# MIDITheremin10-24.net
KiCad netlist of a schematic drawn in EAGLE
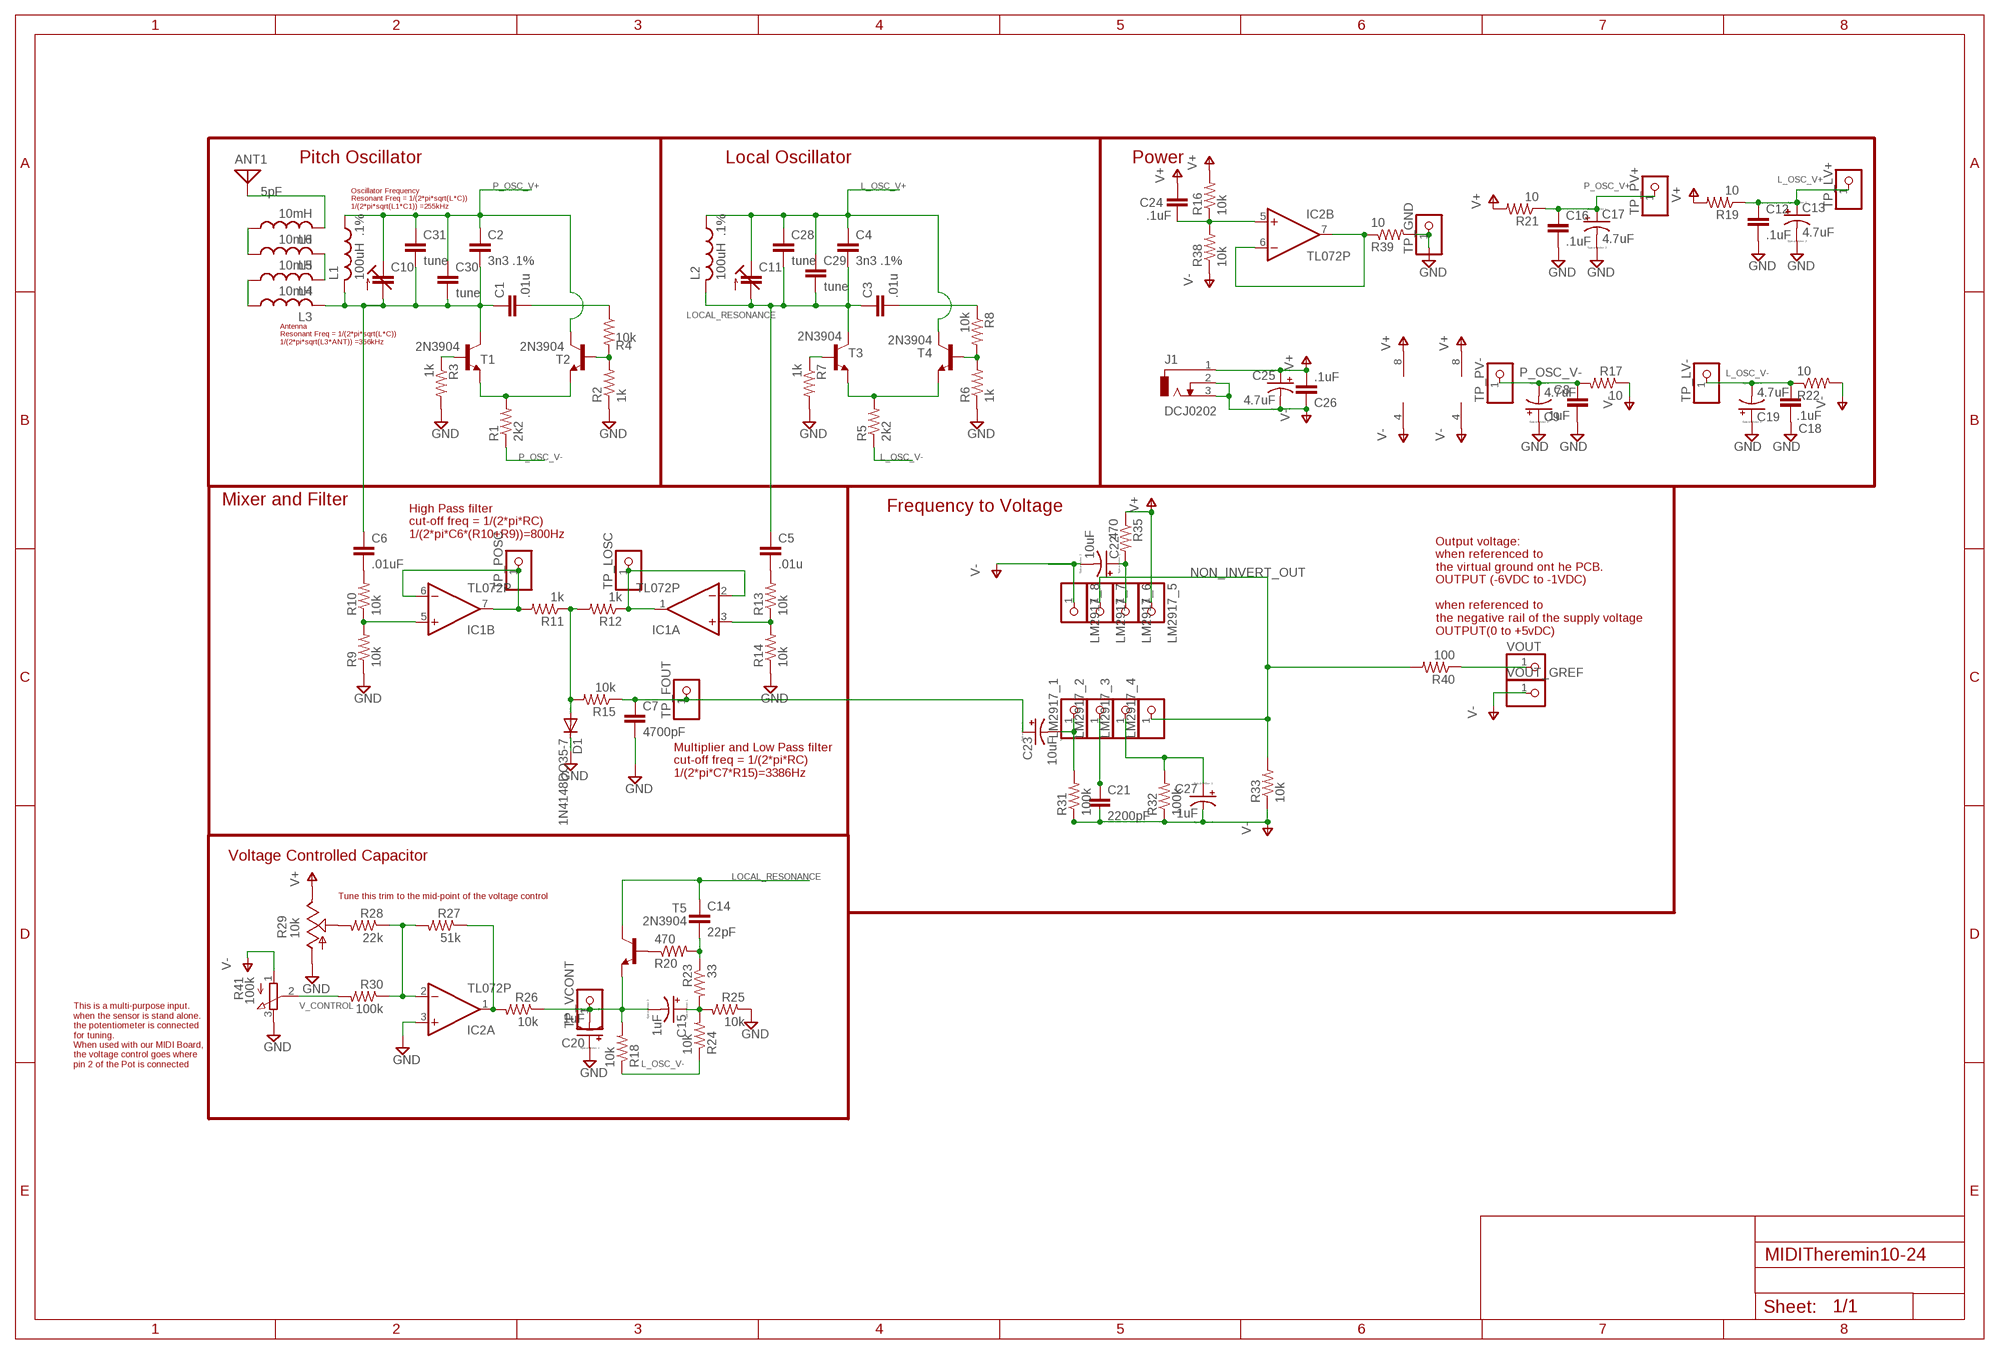
[diagram p0: schematic, sheet 1]

(export (version "E")
  (design (tool "Eeschema 10.0.6"))
  (components
    (comp (ref "ANT1")
      (value "5pF")
      (footprint "eagle-import:PAD-01")
      (libsource (lib "eagle-import") (part "ANTENNA"))
    )
    (comp (ref "C1")
      (value ".01u")
      (footprint "eagle-import:C050-025X075")
      (libsource (lib "eagle-import") (part "C-EU050-025X075"))
    )
    (comp (ref "C2")
      (value "3n3 .1%")
      (footprint "eagle-import:C050-025X075")
      (libsource (lib "eagle-import") (part "C-EU050-025X075"))
    )
    (comp (ref "C3")
      (value ".01u")
      (footprint "eagle-import:C050-025X075")
      (libsource (lib "eagle-import") (part "C-EU050-025X075"))
    )
    (comp (ref "C4")
      (value "3n3 .1%")
      (footprint "eagle-import:C050-025X075")
      (libsource (lib "eagle-import") (part "C-EU050-025X075"))
    )
    (comp (ref "C5")
      (value ".01u")
      (footprint "eagle-import:C050-025X075")
      (libsource (lib "eagle-import") (part "C-EU050-025X075"))
    )
    (comp (ref "C6")
      (value ".01uF")
      (footprint "eagle-import:C050-025X075")
      (libsource (lib "eagle-import") (part "C-EU050-025X075"))
    )
    (comp (ref "C7")
      (value "4700pF")
      (footprint "eagle-import:C050-025X075")
      (libsource (lib "eagle-import") (part "C-EU050-025X075"))
    )
    (comp (ref "C8")
      (value ".1uF")
      (footprint "eagle-import:C050-025X075")
      (libsource (lib "eagle-import") (part "C-EU050-025X075"))
    )
    (comp (ref "C9")
      (value "4.7uF")
      (footprint "eagle-import:E2,5-7")
      (libsource (lib "eagle-import") (part "CPOL-USE2.5-7"))
    )
    (comp (ref "C10")
      (value "C-TRIMM3040.427")
      (footprint "eagle-import:CTRIM3040.427")
      (libsource (lib "eagle-import") (part "C-TRIMM3040.427"))
    )
    (comp (ref "C11")
      (value "C-TRIMM3040.427")
      (footprint "eagle-import:CTRIM3040.427")
      (libsource (lib "eagle-import") (part "C-TRIMM3040.427"))
    )
    (comp (ref "C12")
      (value ".1uF")
      (footprint "eagle-import:C050-025X075")
      (libsource (lib "eagle-import") (part "C-EU050-025X075"))
    )
    (comp (ref "C13")
      (value "4.7uF")
      (footprint "eagle-import:E2,5-7")
      (libsource (lib "eagle-import") (part "CPOL-USE2.5-7"))
    )
    (comp (ref "C14")
      (value "22pF")
      (footprint "eagle-import:C050-025X075")
      (libsource (lib "eagle-import") (part "C-EU050-025X075"))
    )
    (comp (ref "C15")
      (value "1uF")
      (footprint "eagle-import:E2,5-7")
      (libsource (lib "eagle-import") (part "CPOL-USE2.5-7"))
    )
    (comp (ref "C16")
      (value ".1uF")
      (footprint "eagle-import:C050-025X075")
      (libsource (lib "eagle-import") (part "C-EU050-025X075"))
    )
    (comp (ref "C17")
      (value "4.7uF")
      (footprint "eagle-import:E2,5-7")
      (libsource (lib "eagle-import") (part "CPOL-USE2.5-7"))
    )
    (comp (ref "C18")
      (value ".1uF")
      (footprint "eagle-import:C050-025X075")
      (libsource (lib "eagle-import") (part "C-EU050-025X075"))
    )
    (comp (ref "C19")
      (value "4.7uF")
      (footprint "eagle-import:E2,5-7")
      (libsource (lib "eagle-import") (part "CPOL-USE2.5-7"))
    )
    (comp (ref "C20")
      (value "1uF")
      (footprint "eagle-import:E2,5-7")
      (libsource (lib "eagle-import") (part "CPOL-USE2.5-7"))
    )
    (comp (ref "C21")
      (value "2200pF")
      (footprint "eagle-import:C050-025X075")
      (libsource (lib "eagle-import") (part "C-EU050-025X075"))
    )
    (comp (ref "C22")
      (value "10uF")
      (footprint "eagle-import:E2,5-7")
      (libsource (lib "eagle-import") (part "CPOL-USE2.5-7"))
    )
    (comp (ref "C23")
      (value "10uF")
      (footprint "eagle-import:E2,5-7")
      (libsource (lib "eagle-import") (part "CPOL-USE2.5-7"))
    )
    (comp (ref "C24")
      (value ".1uF")
      (footprint "eagle-import:C050-025X075")
      (libsource (lib "eagle-import") (part "C-EU050-025X075"))
    )
    (comp (ref "C25")
      (value "4.7uF")
      (footprint "eagle-import:E2,5-7")
      (libsource (lib "eagle-import") (part "CPOL-USE2.5-7"))
    )
    (comp (ref "C26")
      (value ".1uF")
      (footprint "eagle-import:C050-025X075")
      (libsource (lib "eagle-import") (part "C-EU050-025X075"))
    )
    (comp (ref "C27")
      (value "1uF")
      (footprint "eagle-import:E2,5-7")
      (libsource (lib "eagle-import") (part "CPOL-USE2.5-7"))
    )
    (comp (ref "C28")
      (value "tune")
      (footprint "eagle-import:C050-025X075")
      (libsource (lib "eagle-import") (part "C-EU050-025X075"))
    )
    (comp (ref "C29")
      (value "tune")
      (footprint "eagle-import:C050-025X075")
      (libsource (lib "eagle-import") (part "C-EU050-025X075"))
    )
    (comp (ref "C30")
      (value "tune")
      (footprint "eagle-import:C050-025X075")
      (libsource (lib "eagle-import") (part "C-EU050-025X075"))
    )
    (comp (ref "C31")
      (value "tune")
      (footprint "eagle-import:C050-025X075")
      (libsource (lib "eagle-import") (part "C-EU050-025X075"))
    )
    (comp (ref "D1")
      (value "1N4148DO35-7")
      (footprint "eagle-import:DO35-7")
      (libsource (lib "eagle-import") (part "1N4148DO35-7"))
    )
    (comp (ref "IC1")
      (value "TL072P")
      (footprint "eagle-import:DIL08")
      (libsource (lib "eagle-import") (part "TL072P"))
    )
    (comp (ref "IC2")
      (value "TL072P")
      (footprint "eagle-import:DIL08")
      (libsource (lib "eagle-import") (part "TL072P"))
    )
    (comp (ref "J1")
      (value "DCJ0202")
      (footprint "eagle-import:DCJ0202")
      (libsource (lib "eagle-import") (part "DCJ0202"))
    )
    (comp (ref "L1")
      (value "100uH .1%")
      (footprint "eagle-import:6000-XXXX-RC")
      (libsource (lib "eagle-import") (part "L-US6000-XXX-RC"))
    )
    (comp (ref "L2")
      (value "100uH .1%")
      (footprint "eagle-import:6000-XXXX-RC")
      (libsource (lib "eagle-import") (part "L-US6000-XXX-RC"))
    )
    (comp (ref "L3")
      (value "10mH")
      (footprint "eagle-import:6000-XXXX-RC")
      (libsource (lib "eagle-import") (part "L-US6000-XXX-RC"))
    )
    (comp (ref "L4")
      (value "10mH")
      (footprint "eagle-import:6000-XXXX-RC")
      (libsource (lib "eagle-import") (part "L-US6000-XXX-RC"))
    )
    (comp (ref "L5")
      (value "10mH")
      (footprint "eagle-import:6000-XXXX-RC")
      (libsource (lib "eagle-import") (part "L-US6000-XXX-RC"))
    )
    (comp (ref "L6")
      (value "10mH")
      (footprint "eagle-import:6000-XXXX-RC")
      (libsource (lib "eagle-import") (part "L-US6000-XXX-RC"))
    )
    (comp (ref "LM2917_1")
      (value "PINHD-1X1")
      (footprint "eagle-import:1X01")
      (libsource (lib "eagle-import") (part "PINHD-1X1"))
    )
    (comp (ref "LM2917_2")
      (value "PINHD-1X1")
      (footprint "eagle-import:1X01")
      (libsource (lib "eagle-import") (part "PINHD-1X1"))
    )
    (comp (ref "LM2917_3")
      (value "PINHD-1X1")
      (footprint "eagle-import:1X01")
      (libsource (lib "eagle-import") (part "PINHD-1X1"))
    )
    (comp (ref "LM2917_4")
      (value "PINHD-1X1")
      (footprint "eagle-import:1X01")
      (libsource (lib "eagle-import") (part "PINHD-1X1"))
    )
    (comp (ref "LM2917_5")
      (value "PINHD-1X1")
      (footprint "eagle-import:1X01")
      (libsource (lib "eagle-import") (part "PINHD-1X1"))
    )
    (comp (ref "LM2917_6")
      (value "PINHD-1X1")
      (footprint "eagle-import:1X01")
      (libsource (lib "eagle-import") (part "PINHD-1X1"))
    )
    (comp (ref "LM2917_7")
      (value "PINHD-1X1")
      (footprint "eagle-import:1X01")
      (libsource (lib "eagle-import") (part "PINHD-1X1"))
    )
    (comp (ref "LM2917_8")
      (value "PINHD-1X1")
      (footprint "eagle-import:1X01")
      (libsource (lib "eagle-import") (part "PINHD-1X1"))
    )
    (comp (ref "R1")
      (value "2k2")
      (footprint "eagle-import:0411V")
      (libsource (lib "eagle-import") (part "resistor_R-US_0411/3V"))
    )
    (comp (ref "R2")
      (value "1k")
      (footprint "eagle-import:0411V")
      (libsource (lib "eagle-import") (part "resistor_R-US_0411/3V"))
    )
    (comp (ref "R3")
      (value "1k")
      (footprint "eagle-import:0411V")
      (libsource (lib "eagle-import") (part "resistor_R-US_0411/3V"))
    )
    (comp (ref "R4")
      (value "10k")
      (footprint "eagle-import:0411V")
      (libsource (lib "eagle-import") (part "resistor_R-US_0411/3V"))
    )
    (comp (ref "R5")
      (value "2k2")
      (footprint "eagle-import:0411V")
      (libsource (lib "eagle-import") (part "resistor_R-US_0411/3V"))
    )
    (comp (ref "R6")
      (value "1k")
      (footprint "eagle-import:0411V")
      (libsource (lib "eagle-import") (part "resistor_R-US_0411/3V"))
    )
    (comp (ref "R7")
      (value "1k")
      (footprint "eagle-import:0411V")
      (libsource (lib "eagle-import") (part "resistor_R-US_0411/3V"))
    )
    (comp (ref "R8")
      (value "10k")
      (footprint "eagle-import:0411V")
      (libsource (lib "eagle-import") (part "resistor_R-US_0411/3V"))
    )
    (comp (ref "R9")
      (value "10k")
      (footprint "eagle-import:0411V")
      (libsource (lib "eagle-import") (part "resistor_R-US_0411/3V"))
    )
    (comp (ref "R10")
      (value "10k")
      (footprint "eagle-import:0411V")
      (libsource (lib "eagle-import") (part "resistor_R-US_0411/3V"))
    )
    (comp (ref "R11")
      (value "1k")
      (footprint "eagle-import:0411V")
      (libsource (lib "eagle-import") (part "resistor_R-US_0411/3V"))
    )
    (comp (ref "R12")
      (value "1k")
      (footprint "eagle-import:0411V")
      (libsource (lib "eagle-import") (part "resistor_R-US_0411/3V"))
    )
    (comp (ref "R13")
      (value "10k")
      (footprint "eagle-import:0411V")
      (libsource (lib "eagle-import") (part "resistor_R-US_0411/3V"))
    )
    (comp (ref "R14")
      (value "10k")
      (footprint "eagle-import:0411V")
      (libsource (lib "eagle-import") (part "resistor_R-US_0411/3V"))
    )
    (comp (ref "R15")
      (value "10k")
      (footprint "eagle-import:0411V")
      (libsource (lib "eagle-import") (part "resistor_R-US_0411/3V"))
    )
    (comp (ref "R16")
      (value "10k")
      (footprint "eagle-import:0411V")
      (libsource (lib "eagle-import") (part "resistor_R-US_0411/3V"))
    )
    (comp (ref "R17")
      (value "10")
      (footprint "eagle-import:0411V")
      (libsource (lib "eagle-import") (part "resistor_R-US_0411/3V"))
    )
    (comp (ref "R18")
      (value "10k")
      (footprint "eagle-import:0411V")
      (libsource (lib "eagle-import") (part "resistor_R-US_0411/3V"))
    )
    (comp (ref "R19")
      (value "10")
      (footprint "eagle-import:0411V")
      (libsource (lib "eagle-import") (part "resistor_R-US_0411/3V"))
    )
    (comp (ref "R20")
      (value "470")
      (footprint "eagle-import:0411V")
      (libsource (lib "eagle-import") (part "resistor_R-US_0411/3V"))
    )
    (comp (ref "R21")
      (value "10")
      (footprint "eagle-import:0411V")
      (libsource (lib "eagle-import") (part "resistor_R-US_0411/3V"))
    )
    (comp (ref "R22")
      (value "10")
      (footprint "eagle-import:0411V")
      (libsource (lib "eagle-import") (part "resistor_R-US_0411/3V"))
    )
    (comp (ref "R23")
      (value "33")
      (footprint "eagle-import:0411V")
      (libsource (lib "eagle-import") (part "resistor_R-US_0411/3V"))
    )
    (comp (ref "R24")
      (value "10k")
      (footprint "eagle-import:0411V")
      (libsource (lib "eagle-import") (part "resistor_R-US_0411/3V"))
    )
    (comp (ref "R25")
      (value "10k")
      (footprint "eagle-import:0411V")
      (libsource (lib "eagle-import") (part "resistor_R-US_0411/3V"))
    )
    (comp (ref "R26")
      (value "10k")
      (footprint "eagle-import:0411V")
      (libsource (lib "eagle-import") (part "resistor_R-US_0411/3V"))
    )
    (comp (ref "R27")
      (value "51k")
      (footprint "eagle-import:0411V")
      (libsource (lib "eagle-import") (part "resistor_R-US_0411/3V"))
    )
    (comp (ref "R28")
      (value "22k")
      (footprint "eagle-import:0411V")
      (libsource (lib "eagle-import") (part "resistor_R-US_0411/3V"))
    )
    (comp (ref "R29")
      (value "10k")
      (footprint "eagle-import:B64Y")
      (libsource (lib "eagle-import") (part "TRIM_US-B64Y"))
    )
    (comp (ref "R30")
      (value "100k")
      (footprint "eagle-import:0411V")
      (libsource (lib "eagle-import") (part "resistor_R-US_0411/3V"))
    )
    (comp (ref "R31")
      (value "100k")
      (footprint "eagle-import:0411V")
      (libsource (lib "eagle-import") (part "R-US_0411/3V"))
    )
    (comp (ref "R32")
      (value "100k")
      (footprint "eagle-import:0411V")
      (libsource (lib "eagle-import") (part "R-US_0411/3V"))
    )
    (comp (ref "R33")
      (value "10k")
      (footprint "eagle-import:0411V")
      (libsource (lib "eagle-import") (part "R-US_0411/3V"))
    )
    (comp (ref "R35")
      (value "470")
      (footprint "eagle-import:0411V")
      (libsource (lib "eagle-import") (part "R-US_0411/3V"))
    )
    (comp (ref "R38")
      (value "10k")
      (footprint "eagle-import:0411V")
      (libsource (lib "eagle-import") (part "resistor_R-US_0411/3V"))
    )
    (comp (ref "R39")
      (value "10")
      (footprint "eagle-import:0411V")
      (libsource (lib "eagle-import") (part "resistor_R-US_0411/3V"))
    )
    (comp (ref "R40")
      (value "100")
      (footprint "eagle-import:0411V")
      (libsource (lib "eagle-import") (part "R-US_0411/3V"))
    )
    (comp (ref "R41")
      (value "100k")
      (footprint "eagle-import:3RP_1610N")
      (libsource (lib "eagle-import") (part "3RP/1610N"))
    )
    (comp (ref "T1")
      (value "2N3904")
      (footprint "eagle-import:TO92")
      (libsource (lib "eagle-import") (part "2N3904"))
    )
    (comp (ref "T2")
      (value "2N3904")
      (footprint "eagle-import:TO92")
      (libsource (lib "eagle-import") (part "2N3904"))
    )
    (comp (ref "T3")
      (value "2N3904")
      (footprint "eagle-import:TO92")
      (libsource (lib "eagle-import") (part "2N3904"))
    )
    (comp (ref "T4")
      (value "2N3904")
      (footprint "eagle-import:TO92")
      (libsource (lib "eagle-import") (part "2N3904"))
    )
    (comp (ref "T5")
      (value "2N3904")
      (footprint "eagle-import:TO92")
      (libsource (lib "eagle-import") (part "2N3904"))
    )
    (comp (ref "TP_FOUT")
      (value "PINHD-1X1")
      (footprint "eagle-import:1X01")
      (libsource (lib "eagle-import") (part "PINHD-1X1"))
    )
    (comp (ref "TP_GND")
      (value "PINHD-1X1")
      (footprint "eagle-import:1X01")
      (libsource (lib "eagle-import") (part "PINHD-1X1"))
    )
    (comp (ref "TP_LOSC")
      (value "PINHD-1X1")
      (footprint "eagle-import:1X01")
      (libsource (lib "eagle-import") (part "PINHD-1X1"))
    )
    (comp (ref "TP_LV+")
      (value "PINHD-1X1")
      (footprint "eagle-import:1X01")
      (libsource (lib "eagle-import") (part "PINHD-1X1"))
    )
    (comp (ref "TP_LV-")
      (value "PINHD-1X1")
      (footprint "eagle-import:1X01")
      (libsource (lib "eagle-import") (part "PINHD-1X1"))
    )
    (comp (ref "TP_POSC")
      (value "PINHD-1X1")
      (footprint "eagle-import:1X01")
      (libsource (lib "eagle-import") (part "PINHD-1X1"))
    )
    (comp (ref "TP_PV+")
      (value "PINHD-1X1")
      (footprint "eagle-import:1X01")
      (libsource (lib "eagle-import") (part "PINHD-1X1"))
    )
    (comp (ref "TP_PV-")
      (value "PINHD-1X1")
      (footprint "eagle-import:1X01")
      (libsource (lib "eagle-import") (part "PINHD-1X1"))
    )
    (comp (ref "TP_VCONT")
      (value "PINHD-1X1")
      (footprint "eagle-import:1X01")
      (libsource (lib "eagle-import") (part "PINHD-1X1"))
    )
    (comp (ref "VOUT")
      (value "PINHD-1X1")
      (footprint "eagle-import:1X01")
      (libsource (lib "eagle-import") (part "PINHD-1X1"))
    )
    (comp (ref "VOUT_GREF")
      (value "PINHD-1X1")
      (footprint "eagle-import:1X01")
      (libsource (lib "eagle-import") (part "PINHD-1X1"))
    )
  )
  (nets
    (net (code "1") (name "/LOCAL_RESONANCE") (class "Default")
      (node (ref "C11") (pin "2") (pinfunction "A_2") (pintype "passive"))
      (node (ref "C14") (pin "1") (pinfunction "1_1") (pintype "passive"))
      (node (ref "C28") (pin "2") (pinfunction "2_2") (pintype "passive"))
      (node (ref "C29") (pin "2") (pinfunction "2_2") (pintype "passive"))
      (node (ref "C3") (pin "1") (pinfunction "1_1") (pintype "passive"))
      (node (ref "C4") (pin "2") (pinfunction "2_2") (pintype "passive"))
      (node (ref "C5") (pin "1") (pinfunction "1_1") (pintype "passive"))
      (node (ref "L2") (pin "2") (pinfunction "2_2") (pintype "passive"))
      (node (ref "T3") (pin "1") (pinfunction "C_1") (pintype "passive"))
      (node (ref "T5") (pin "1") (pinfunction "C_1") (pintype "passive"))
    )
    (net (code "2") (name "/L_OSC_V+") (class "Default")
      (node (ref "C11") (pin "1A") (pinfunction "E_1A") (pintype "passive"))
      (node (ref "C12") (pin "1") (pinfunction "1_1") (pintype "passive"))
      (node (ref "C13") (pin "+") (pinfunction "+_+") (pintype "passive"))
      (node (ref "C28") (pin "1") (pinfunction "1_1") (pintype "passive"))
      (node (ref "C29") (pin "1") (pinfunction "1_1") (pintype "passive"))
      (node (ref "C4") (pin "1") (pinfunction "1_1") (pintype "passive"))
      (node (ref "L2") (pin "1") (pinfunction "1_1") (pintype "passive"))
      (node (ref "R19") (pin "1") (pinfunction "1_1") (pintype "passive"))
      (node (ref "T4") (pin "1") (pinfunction "C_1") (pintype "passive"))
      (node (ref "TP_LV+") (pin "1") (pinfunction "1_1") (pintype "passive"))
    )
    (net (code "3") (name "/L_OSC_V-") (class "Default")
      (node (ref "C18") (pin "1") (pinfunction "1_1") (pintype "passive"))
      (node (ref "C19") (pin "-") (pinfunction "-_-") (pintype "passive"))
      (node (ref "R18") (pin "1") (pinfunction "1_1") (pintype "passive"))
      (node (ref "R22") (pin "1") (pinfunction "1_1") (pintype "passive"))
      (node (ref "R24") (pin "1") (pinfunction "1_1") (pintype "passive"))
      (node (ref "R5") (pin "1") (pinfunction "1_1") (pintype "passive"))
      (node (ref "TP_LV-") (pin "1") (pinfunction "1_1") (pintype "passive"))
    )
    (net (code "4") (name "/NON_INVERT_OUT") (class "Default")
      (node (ref "LM2917_4") (pin "1") (pinfunction "1_1") (pintype "passive"))
      (node (ref "LM2917_7") (pin "1") (pinfunction "1_1") (pintype "passive"))
      (node (ref "R33") (pin "2") (pinfunction "2_2") (pintype "passive"))
      (node (ref "R40") (pin "2") (pinfunction "2_2") (pintype "passive"))
    )
    (net (code "5") (name "/P_OSC_V+") (class "Default")
      (node (ref "C10") (pin "1A") (pinfunction "E_1A") (pintype "passive"))
      (node (ref "C16") (pin "1") (pinfunction "1_1") (pintype "passive"))
      (node (ref "C17") (pin "+") (pinfunction "+_+") (pintype "passive"))
      (node (ref "C2") (pin "1") (pinfunction "1_1") (pintype "passive"))
      (node (ref "C30") (pin "1") (pinfunction "1_1") (pintype "passive"))
      (node (ref "C31") (pin "1") (pinfunction "1_1") (pintype "passive"))
      (node (ref "L1") (pin "1") (pinfunction "1_1") (pintype "passive"))
      (node (ref "R21") (pin "1") (pinfunction "1_1") (pintype "passive"))
      (node (ref "T2") (pin "1") (pinfunction "C_1") (pintype "passive"))
      (node (ref "TP_PV+") (pin "1") (pinfunction "1_1") (pintype "passive"))
    )
    (net (code "6") (name "/P_OSC_V-") (class "Default")
      (node (ref "C8") (pin "1") (pinfunction "1_1") (pintype "passive"))
      (node (ref "C9") (pin "-") (pinfunction "-_-") (pintype "passive"))
      (node (ref "R1") (pin "1") (pinfunction "1_1") (pintype "passive"))
      (node (ref "R17") (pin "2") (pinfunction "2_2") (pintype "passive"))
      (node (ref "TP_PV-") (pin "1") (pinfunction "1_1") (pintype "passive"))
    )
    (net (code "7") (name "/V_CONTROL") (class "Default")
      (node (ref "R30") (pin "2") (pinfunction "2_2") (pintype "passive"))
      (node (ref "R41") (pin "2") (pinfunction "S_2") (pintype "passive"))
    )
    (net (code "8") (name "GND") (class "Default")
      (node (ref "C12") (pin "2") (pinfunction "2_2") (pintype "passive"))
      (node (ref "C13") (pin "-") (pinfunction "-_-") (pintype "passive"))
      (node (ref "C16") (pin "2") (pinfunction "2_2") (pintype "passive"))
      (node (ref "C17") (pin "-") (pinfunction "-_-") (pintype "passive"))
      (node (ref "C18") (pin "2") (pinfunction "2_2") (pintype "passive"))
      (node (ref "C19") (pin "+") (pinfunction "+_+") (pintype "passive"))
      (node (ref "C20") (pin "+") (pinfunction "+_+") (pintype "passive"))
      (node (ref "C7") (pin "2") (pinfunction "2_2") (pintype "passive"))
      (node (ref "C8") (pin "2") (pinfunction "2_2") (pintype "passive"))
      (node (ref "C9") (pin "+") (pinfunction "+_+") (pintype "passive"))
      (node (ref "D1") (pin "C") (pinfunction "C_C") (pintype "passive"))
      (node (ref "IC2") (pin "3") (pinfunction "+IN_3") (pintype "input"))
      (node (ref "R14") (pin "1") (pinfunction "1_1") (pintype "passive"))
      (node (ref "R2") (pin "1") (pinfunction "1_1") (pintype "passive"))
      (node (ref "R25") (pin "1") (pinfunction "1_1") (pintype "passive"))
      (node (ref "R29") (pin "A") (pinfunction "A_A") (pintype "passive"))
      (node (ref "R3") (pin "2") (pinfunction "2_2") (pintype "passive"))
      (node (ref "R39") (pin "2") (pinfunction "2_2") (pintype "passive"))
      (node (ref "R41") (pin "3") (pinfunction "E_3") (pintype "passive"))
      (node (ref "R6") (pin "1") (pinfunction "1_1") (pintype "passive"))
      (node (ref "R7") (pin "2") (pinfunction "2_2") (pintype "passive"))
      (node (ref "R9") (pin "1") (pinfunction "1_1") (pintype "passive"))
      (node (ref "TP_GND") (pin "1") (pinfunction "1_1") (pintype "passive"))
    )
    (net (code "9") (name "Net-(ANT1-Pad1)") (class "Default")
      (node (ref "ANT1") (pin "1") (pinfunction "1_1") (pintype "output"))
      (node (ref "L6") (pin "2") (pinfunction "2_2") (pintype "passive"))
    )
    (net (code "10") (name "Net-(C1-Pad2)") (class "Default")
      (node (ref "C1") (pin "2") (pinfunction "2_2") (pintype "passive"))
      (node (ref "R4") (pin "1") (pinfunction "1_1") (pintype "passive"))
    )
    (net (code "11") (name "Net-(C3-Pad2)") (class "Default")
      (node (ref "C3") (pin "2") (pinfunction "2_2") (pintype "passive"))
      (node (ref "R8") (pin "1") (pinfunction "1_1") (pintype "passive"))
    )
    (net (code "12") (name "Net-(C5-Pad2)") (class "Default")
      (node (ref "C5") (pin "2") (pinfunction "2_2") (pintype "passive"))
      (node (ref "R13") (pin "2") (pinfunction "2_2") (pintype "passive"))
    )
    (net (code "13") (name "Net-(C6-Pad2)") (class "Default")
      (node (ref "C6") (pin "2") (pinfunction "2_2") (pintype "passive"))
      (node (ref "R10") (pin "2") (pinfunction "2_2") (pintype "passive"))
    )
    (net (code "14") (name "Net-(C10-A)") (class "Default")
      (node (ref "C1") (pin "1") (pinfunction "1_1") (pintype "passive"))
      (node (ref "C10") (pin "2") (pinfunction "A_2") (pintype "passive"))
      (node (ref "C2") (pin "2") (pinfunction "2_2") (pintype "passive"))
      (node (ref "C30") (pin "2") (pinfunction "2_2") (pintype "passive"))
      (node (ref "C31") (pin "2") (pinfunction "2_2") (pintype "passive"))
      (node (ref "C6") (pin "1") (pinfunction "1_1") (pintype "passive"))
      (node (ref "L1") (pin "2") (pinfunction "2_2") (pintype "passive"))
      (node (ref "L3") (pin "2") (pinfunction "2_2") (pintype "passive"))
      (node (ref "T1") (pin "1") (pinfunction "C_1") (pintype "passive"))
    )
    (net (code "15") (name "Net-(C14-Pad2)") (class "Default")
      (node (ref "C14") (pin "2") (pinfunction "2_2") (pintype "passive"))
      (node (ref "R20") (pin "2") (pinfunction "2_2") (pintype "passive"))
      (node (ref "R23") (pin "1") (pinfunction "1_1") (pintype "passive"))
    )
    (net (code "16") (name "Net-(C15-Pad+)") (class "Default")
      (node (ref "C15") (pin "+") (pinfunction "+_+") (pintype "passive"))
      (node (ref "R23") (pin "2") (pinfunction "2_2") (pintype "passive"))
      (node (ref "R24") (pin "2") (pinfunction "2_2") (pintype "passive"))
      (node (ref "R25") (pin "2") (pinfunction "2_2") (pintype "passive"))
    )
    (net (code "17") (name "Net-(C21-Pad1)") (class "Default")
      (node (ref "C21") (pin "1") (pinfunction "1_1") (pintype "passive"))
      (node (ref "LM2917_2") (pin "1") (pinfunction "1_1") (pintype "passive"))
    )
    (net (code "18") (name "Net-(C22-Pad+)") (class "Default")
      (node (ref "C22") (pin "+") (pinfunction "+_+") (pintype "passive"))
      (node (ref "LM2917_6") (pin "1") (pinfunction "1_1") (pintype "passive"))
      (node (ref "R35") (pin "2") (pinfunction "2_2") (pintype "passive"))
    )
    (net (code "19") (name "Net-(C23-Pad+)") (class "Default")
      (node (ref "C23") (pin "+") (pinfunction "+_+") (pintype "passive"))
      (node (ref "C7") (pin "1") (pinfunction "1_1") (pintype "passive"))
      (node (ref "R15") (pin "1") (pinfunction "1_1") (pintype "passive"))
      (node (ref "TP_FOUT") (pin "1") (pinfunction "1_1") (pintype "passive"))
    )
    (net (code "20") (name "Net-(C23-Pad-)") (class "Default")
      (node (ref "C23") (pin "-") (pinfunction "-_-") (pintype "passive"))
      (node (ref "LM2917_1") (pin "1") (pinfunction "1_1") (pintype "passive"))
      (node (ref "R31") (pin "2") (pinfunction "2_2") (pintype "passive"))
    )
    (net (code "21") (name "Net-(C27-Pad+)") (class "Default")
      (node (ref "C27") (pin "+") (pinfunction "+_+") (pintype "passive"))
      (node (ref "LM2917_3") (pin "1") (pinfunction "1_1") (pintype "passive"))
      (node (ref "R32") (pin "2") (pinfunction "2_2") (pintype "passive"))
    )
    (net (code "22") (name "Net-(D1-PadA)") (class "Default")
      (node (ref "D1") (pin "A") (pinfunction "A_A") (pintype "passive"))
      (node (ref "R11") (pin "1") (pinfunction "1_1") (pintype "passive"))
      (node (ref "R12") (pin "2") (pinfunction "2_2") (pintype "passive"))
      (node (ref "R15") (pin "2") (pinfunction "2_2") (pintype "passive"))
    )
    (net (code "23") (name "Net-(IC1A-+IN)") (class "Default")
      (node (ref "IC1") (pin "3") (pinfunction "+IN_3") (pintype "input"))
      (node (ref "R13") (pin "1") (pinfunction "1_1") (pintype "passive"))
      (node (ref "R14") (pin "2") (pinfunction "2_2") (pintype "passive"))
    )
    (net (code "24") (name "Net-(IC1A--IN)") (class "Default")
      (node (ref "IC1") (pin "1") (pinfunction "OUT_1") (pintype "output"))
      (node (ref "IC1") (pin "2") (pinfunction "-IN_2") (pintype "input"))
      (node (ref "R12") (pin "1") (pinfunction "1_1") (pintype "passive"))
      (node (ref "TP_LOSC") (pin "1") (pinfunction "1_1") (pintype "passive"))
    )
    (net (code "25") (name "Net-(IC1B-+IN)") (class "Default")
      (node (ref "IC1") (pin "5") (pinfunction "+IN_5") (pintype "input"))
      (node (ref "R10") (pin "1") (pinfunction "1_1") (pintype "passive"))
      (node (ref "R9") (pin "2") (pinfunction "2_2") (pintype "passive"))
    )
    (net (code "26") (name "Net-(IC1B--IN)") (class "Default")
      (node (ref "IC1") (pin "6") (pinfunction "-IN_6") (pintype "input"))
      (node (ref "IC1") (pin "7") (pinfunction "OUT_7") (pintype "output"))
      (node (ref "R11") (pin "2") (pinfunction "2_2") (pintype "passive"))
      (node (ref "TP_POSC") (pin "1") (pinfunction "1_1") (pintype "passive"))
    )
    (net (code "27") (name "Net-(IC2A--IN)") (class "Default")
      (node (ref "IC2") (pin "2") (pinfunction "-IN_2") (pintype "input"))
      (node (ref "R27") (pin "2") (pinfunction "2_2") (pintype "passive"))
      (node (ref "R28") (pin "1") (pinfunction "1_1") (pintype "passive"))
      (node (ref "R30") (pin "1") (pinfunction "1_1") (pintype "passive"))
    )
    (net (code "28") (name "Net-(IC2A-OUT)") (class "Default")
      (node (ref "IC2") (pin "1") (pinfunction "OUT_1") (pintype "output"))
      (node (ref "R26") (pin "2") (pinfunction "2_2") (pintype "passive"))
      (node (ref "R27") (pin "1") (pinfunction "1_1") (pintype "passive"))
    )
    (net (code "29") (name "Net-(IC2B-+IN)") (class "Default")
      (node (ref "C24") (pin "2") (pinfunction "2_2") (pintype "passive"))
      (node (ref "IC2") (pin "5") (pinfunction "+IN_5") (pintype "input"))
      (node (ref "R16") (pin "1") (pinfunction "1_1") (pintype "passive"))
      (node (ref "R38") (pin "2") (pinfunction "2_2") (pintype "passive"))
    )
    (net (code "30") (name "Net-(IC2B--IN)") (class "Default")
      (node (ref "IC2") (pin "6") (pinfunction "-IN_6") (pintype "input"))
      (node (ref "IC2") (pin "7") (pinfunction "OUT_7") (pintype "output"))
      (node (ref "R39") (pin "1") (pinfunction "1_1") (pintype "passive"))
    )
    (net (code "31") (name "Net-(L3-Pad1)") (class "Default")
      (node (ref "L3") (pin "1") (pinfunction "1_1") (pintype "passive"))
      (node (ref "L4") (pin "1") (pinfunction "1_1") (pintype "passive"))
    )
    (net (code "32") (name "Net-(L4-Pad2)") (class "Default")
      (node (ref "L4") (pin "2") (pinfunction "2_2") (pintype "passive"))
      (node (ref "L5") (pin "2") (pinfunction "2_2") (pintype "passive"))
    )
    (net (code "33") (name "Net-(L5-Pad1)") (class "Default")
      (node (ref "L5") (pin "1") (pinfunction "1_1") (pintype "passive"))
      (node (ref "L6") (pin "1") (pinfunction "1_1") (pintype "passive"))
    )
    (net (code "34") (name "Net-(R28-Pad2)") (class "Default")
      (node (ref "R28") (pin "2") (pinfunction "2_2") (pintype "passive"))
      (node (ref "R29") (pin "S") (pinfunction "S_S") (pintype "passive"))
    )
    (net (code "35") (name "Net-(R40-Pad1)") (class "Default")
      (node (ref "R40") (pin "1") (pinfunction "1_1") (pintype "passive"))
      (node (ref "VOUT") (pin "1") (pinfunction "1_1") (pintype "passive"))
    )
    (net (code "36") (name "Net-(T1-B)") (class "Default")
      (node (ref "R3") (pin "1") (pinfunction "1_1") (pintype "passive"))
      (node (ref "T1") (pin "2") (pinfunction "B_2") (pintype "passive"))
    )
    (net (code "37") (name "Net-(T1-E)") (class "Default")
      (node (ref "R1") (pin "2") (pinfunction "2_2") (pintype "passive"))
      (node (ref "T1") (pin "3") (pinfunction "E_3") (pintype "passive"))
      (node (ref "T2") (pin "3") (pinfunction "E_3") (pintype "passive"))
    )
    (net (code "38") (name "Net-(T2-B)") (class "Default")
      (node (ref "R2") (pin "2") (pinfunction "2_2") (pintype "passive"))
      (node (ref "R4") (pin "2") (pinfunction "2_2") (pintype "passive"))
      (node (ref "T2") (pin "2") (pinfunction "B_2") (pintype "passive"))
    )
    (net (code "39") (name "Net-(T3-B)") (class "Default")
      (node (ref "R7") (pin "1") (pinfunction "1_1") (pintype "passive"))
      (node (ref "T3") (pin "2") (pinfunction "B_2") (pintype "passive"))
    )
    (net (code "40") (name "Net-(T3-E)") (class "Default")
      (node (ref "R5") (pin "2") (pinfunction "2_2") (pintype "passive"))
      (node (ref "T3") (pin "3") (pinfunction "E_3") (pintype "passive"))
      (node (ref "T4") (pin "3") (pinfunction "E_3") (pintype "passive"))
    )
    (net (code "41") (name "Net-(T4-B)") (class "Default")
      (node (ref "R6") (pin "2") (pinfunction "2_2") (pintype "passive"))
      (node (ref "R8") (pin "2") (pinfunction "2_2") (pintype "passive"))
      (node (ref "T4") (pin "2") (pinfunction "B_2") (pintype "passive"))
    )
    (net (code "42") (name "Net-(T5-B)") (class "Default")
      (node (ref "R20") (pin "1") (pinfunction "1_1") (pintype "passive"))
      (node (ref "T5") (pin "2") (pinfunction "B_2") (pintype "passive"))
    )
    (net (code "43") (name "Net-(T5-E)") (class "Default")
      (node (ref "C15") (pin "-") (pinfunction "-_-") (pintype "passive"))
      (node (ref "C20") (pin "-") (pinfunction "-_-") (pintype "passive"))
      (node (ref "R18") (pin "2") (pinfunction "2_2") (pintype "passive"))
      (node (ref "R26") (pin "1") (pinfunction "1_1") (pintype "passive"))
      (node (ref "T5") (pin "3") (pinfunction "E_3") (pintype "passive"))
      (node (ref "TP_VCONT") (pin "1") (pinfunction "1_1") (pintype "passive"))
    )
    (net (code "44") (name "V+") (class "Default")
      (node (ref "C24") (pin "1") (pinfunction "1_1") (pintype "passive"))
      (node (ref "C25") (pin "+") (pinfunction "+_+") (pintype "passive"))
      (node (ref "C26") (pin "2") (pinfunction "2_2") (pintype "passive"))
      (node (ref "IC1") (pin "8") (pinfunction "V+_8") (pintype "power_in"))
      (node (ref "IC2") (pin "8") (pinfunction "V+_8") (pintype "power_in"))
      (node (ref "J1") (pin "1") (pinfunction "1_1") (pintype "passive"))
      (node (ref "LM2917_5") (pin "1") (pinfunction "1_1") (pintype "passive"))
      (node (ref "R16") (pin "2") (pinfunction "2_2") (pintype "passive"))
      (node (ref "R19") (pin "2") (pinfunction "2_2") (pintype "passive"))
      (node (ref "R21") (pin "2") (pinfunction "2_2") (pintype "passive"))
      (node (ref "R29") (pin "E") (pinfunction "E_E") (pintype "passive"))
      (node (ref "R35") (pin "1") (pinfunction "1_1") (pintype "passive"))
    )
    (net (code "45") (name "V-") (class "Default")
      (node (ref "C21") (pin "2") (pinfunction "2_2") (pintype "passive"))
      (node (ref "C22") (pin "-") (pinfunction "-_-") (pintype "passive"))
      (node (ref "C25") (pin "-") (pinfunction "-_-") (pintype "passive"))
      (node (ref "C26") (pin "1") (pinfunction "1_1") (pintype "passive"))
      (node (ref "C27") (pin "-") (pinfunction "-_-") (pintype "passive"))
      (node (ref "IC1") (pin "4") (pinfunction "V-_4") (pintype "power_in"))
      (node (ref "IC2") (pin "4") (pinfunction "V-_4") (pintype "power_in"))
      (node (ref "J1") (pin "2") (pinfunction "2_2") (pintype "passive"))
      (node (ref "J1") (pin "3") (pinfunction "3_3") (pintype "passive"))
      (node (ref "LM2917_8") (pin "1") (pinfunction "1_1") (pintype "passive"))
      (node (ref "R17") (pin "1") (pinfunction "1_1") (pintype "passive"))
      (node (ref "R22") (pin "2") (pinfunction "2_2") (pintype "passive"))
      (node (ref "R31") (pin "1") (pinfunction "1_1") (pintype "passive"))
      (node (ref "R32") (pin "1") (pinfunction "1_1") (pintype "passive"))
      (node (ref "R33") (pin "1") (pinfunction "1_1") (pintype "passive"))
      (node (ref "R38") (pin "1") (pinfunction "1_1") (pintype "passive"))
      (node (ref "R41") (pin "1") (pinfunction "A_1") (pintype "passive"))
      (node (ref "VOUT_GREF") (pin "1") (pinfunction "1_1") (pintype "passive"))
    )
  )
)
